# Connecters.net
KiCad netlist of a schematic drawn in Altium Designer
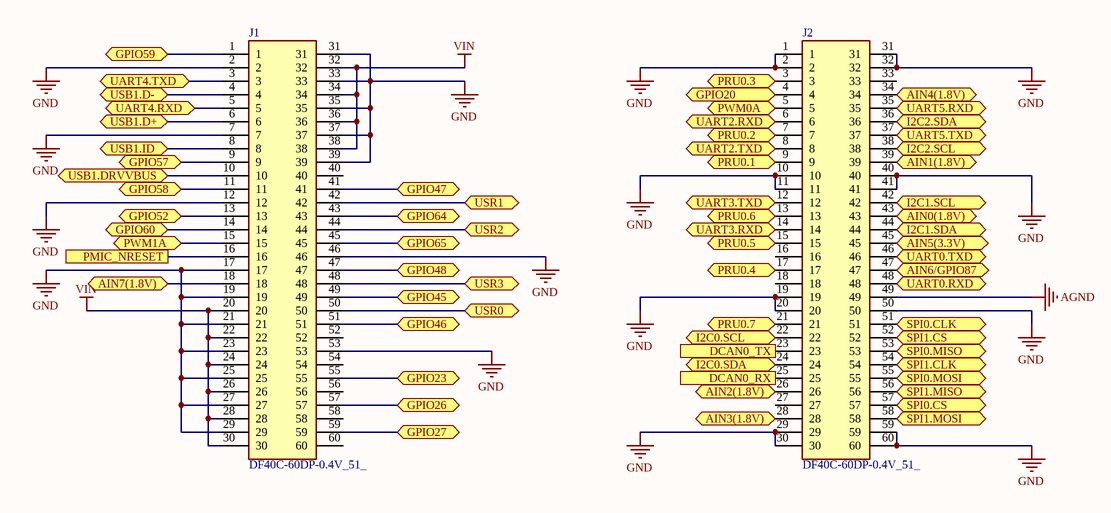
[diagram p0: Connecters.SchDoc]

(export (version "E")
  (design (tool "Eeschema 10.0.6"))
  (components
    (comp (ref "J1")
      (value "DF40C-60DP-0.4V_51_")
      (footprint "SamacSys:DF40C-60DP-0.4V(51)")
      (description "Connector")
      (fields
        (field (name "MANUFACTURER_PART_NUMBER") "DF40C-60DP-0.4V(51)")
        (field (name "MOUSER PART NUMBER") "798-DF40C60DP0.4V51")
      )
      (libsource (lib "Schlib1") (part "DF40C-60DP-0.4V_51_"))
    )
    (comp (ref "J2")
      (value "DF40C-60DP-0.4V_51_")
      (footprint "SamacSys:DF40C-60DP-0.4V(51)")
      (description "Connector")
      (fields
        (field (name "MANUFACTURER_PART_NUMBER") "DF40C-60DP-0.4V(51)")
        (field (name "MOUSER PART NUMBER") "798-DF40C60DP0.4V51")
      )
      (libsource (lib "Schlib1") (part "DF40C-60DP-0.4V_51_"))
    )
  )
  (nets
    (net (code "1") (name "/AIN0(1.8V)") (class "Default")
      (node (ref "J2") (pin "43") (pinfunction "43_43") (pintype "passive"))
    )
    (net (code "2") (name "/AIN1(1.8V)") (class "Default")
      (node (ref "J2") (pin "39") (pinfunction "39_39") (pintype "passive"))
    )
    (net (code "3") (name "/AIN2(1.8V)") (class "Default")
      (node (ref "J2") (pin "26") (pinfunction "26_26") (pintype "passive"))
    )
    (net (code "4") (name "/AIN3(1.8V)") (class "Default")
      (node (ref "J2") (pin "28") (pinfunction "28_28") (pintype "passive"))
    )
    (net (code "5") (name "/AIN4(1.8V)") (class "Default")
      (node (ref "J2") (pin "34") (pinfunction "34_34") (pintype "passive"))
    )
    (net (code "6") (name "/AIN5(3.3V)") (class "Default")
      (node (ref "J2") (pin "45") (pinfunction "45_45") (pintype "passive"))
    )
    (net (code "7") (name "/AIN6{slash}GPIO87") (class "Default")
      (node (ref "J2") (pin "47") (pinfunction "47_47") (pintype "passive"))
    )
    (net (code "8") (name "/AIN7(1.8V)") (class "Default")
      (node (ref "J1") (pin "18") (pinfunction "18_18") (pintype "passive"))
    )
    (net (code "9") (name "/DCAN0_RX") (class "Default")
      (node (ref "J2") (pin "25") (pinfunction "25_25") (pintype "passive"))
    )
    (net (code "10") (name "/DCAN0_TX") (class "Default")
      (node (ref "J2") (pin "23") (pinfunction "23_23") (pintype "passive"))
    )
    (net (code "11") (name "/GPIO20") (class "Default")
      (node (ref "J2") (pin "4") (pinfunction "4_4") (pintype "passive"))
    )
    (net (code "12") (name "/GPIO23") (class "Default")
      (node (ref "J1") (pin "55") (pinfunction "55_55") (pintype "passive"))
    )
    (net (code "13") (name "/GPIO26") (class "Default")
      (node (ref "J1") (pin "57") (pinfunction "57_57") (pintype "passive"))
    )
    (net (code "14") (name "/GPIO27") (class "Default")
      (node (ref "J1") (pin "59") (pinfunction "59_59") (pintype "passive"))
    )
    (net (code "15") (name "/GPIO45") (class "Default")
      (node (ref "J1") (pin "49") (pinfunction "49_49") (pintype "passive"))
    )
    (net (code "16") (name "/GPIO46") (class "Default")
      (node (ref "J1") (pin "51") (pinfunction "51_51") (pintype "passive"))
    )
    (net (code "17") (name "/GPIO47") (class "Default")
      (node (ref "J1") (pin "41") (pinfunction "41_41") (pintype "passive"))
    )
    (net (code "18") (name "/GPIO48") (class "Default")
      (node (ref "J1") (pin "47") (pinfunction "47_47") (pintype "passive"))
    )
    (net (code "19") (name "/GPIO52") (class "Default")
      (node (ref "J1") (pin "13") (pinfunction "13_13") (pintype "passive"))
    )
    (net (code "20") (name "/GPIO57") (class "Default")
      (node (ref "J1") (pin "9") (pinfunction "9_9") (pintype "passive"))
    )
    (net (code "21") (name "/GPIO58") (class "Default")
      (node (ref "J1") (pin "11") (pinfunction "11_11") (pintype "passive"))
    )
    (net (code "22") (name "/GPIO59") (class "Default")
      (node (ref "J1") (pin "1") (pinfunction "1_1") (pintype "passive"))
    )
    (net (code "23") (name "/GPIO60") (class "Default")
      (node (ref "J1") (pin "14") (pinfunction "14_14") (pintype "passive"))
    )
    (net (code "24") (name "/GPIO64") (class "Default")
      (node (ref "J1") (pin "43") (pinfunction "43_43") (pintype "passive"))
    )
    (net (code "25") (name "/GPIO65") (class "Default")
      (node (ref "J1") (pin "45") (pinfunction "45_45") (pintype "passive"))
    )
    (net (code "26") (name "/I2C0.SCL") (class "Default")
      (node (ref "J2") (pin "22") (pinfunction "22_22") (pintype "passive"))
    )
    (net (code "27") (name "/I2C0.SDA") (class "Default")
      (node (ref "J2") (pin "24") (pinfunction "24_24") (pintype "passive"))
    )
    (net (code "28") (name "/I2C1.SCL") (class "Default")
      (node (ref "J2") (pin "42") (pinfunction "42_42") (pintype "passive"))
    )
    (net (code "29") (name "/I2C1.SDA") (class "Default")
      (node (ref "J2") (pin "44") (pinfunction "44_44") (pintype "passive"))
    )
    (net (code "30") (name "/I2C2.SCL") (class "Default")
      (node (ref "J2") (pin "38") (pinfunction "38_38") (pintype "passive"))
    )
    (net (code "31") (name "/I2C2.SDA") (class "Default")
      (node (ref "J2") (pin "36") (pinfunction "36_36") (pintype "passive"))
    )
    (net (code "32") (name "/PMIC_NRESET") (class "Default")
      (node (ref "J1") (pin "16") (pinfunction "16_16") (pintype "passive"))
    )
    (net (code "33") (name "/PRU0.1") (class "Default")
      (node (ref "J2") (pin "9") (pinfunction "9_9") (pintype "passive"))
    )
    (net (code "34") (name "/PRU0.2") (class "Default")
      (node (ref "J2") (pin "7") (pinfunction "7_7") (pintype "passive"))
    )
    (net (code "35") (name "/PRU0.3") (class "Default")
      (node (ref "J2") (pin "3") (pinfunction "3_3") (pintype "passive"))
    )
    (net (code "36") (name "/PRU0.4") (class "Default")
      (node (ref "J2") (pin "17") (pinfunction "17_17") (pintype "passive"))
    )
    (net (code "37") (name "/PRU0.5") (class "Default")
      (node (ref "J2") (pin "15") (pinfunction "15_15") (pintype "passive"))
    )
    (net (code "38") (name "/PRU0.6") (class "Default")
      (node (ref "J2") (pin "13") (pinfunction "13_13") (pintype "passive"))
    )
    (net (code "39") (name "/PRU0.7") (class "Default")
      (node (ref "J2") (pin "21") (pinfunction "21_21") (pintype "passive"))
    )
    (net (code "40") (name "/PWM0A") (class "Default")
      (node (ref "J2") (pin "5") (pinfunction "5_5") (pintype "passive"))
    )
    (net (code "41") (name "/PWM1A") (class "Default")
      (node (ref "J1") (pin "15") (pinfunction "15_15") (pintype "passive"))
    )
    (net (code "42") (name "/SPI0.CLK") (class "Default")
      (node (ref "J2") (pin "51") (pinfunction "51_51") (pintype "passive"))
    )
    (net (code "43") (name "/SPI0.CS") (class "Default")
      (node (ref "J2") (pin "57") (pinfunction "57_57") (pintype "passive"))
    )
    (net (code "44") (name "/SPI0.MISO") (class "Default")
      (node (ref "J2") (pin "53") (pinfunction "53_53") (pintype "passive"))
    )
    (net (code "45") (name "/SPI0.MOSI") (class "Default")
      (node (ref "J2") (pin "55") (pinfunction "55_55") (pintype "passive"))
    )
    (net (code "46") (name "/SPI1.CLK") (class "Default")
      (node (ref "J2") (pin "54") (pinfunction "54_54") (pintype "passive"))
    )
    (net (code "47") (name "/SPI1.CS") (class "Default")
      (node (ref "J2") (pin "52") (pinfunction "52_52") (pintype "passive"))
    )
    (net (code "48") (name "/SPI1.MISO") (class "Default")
      (node (ref "J2") (pin "56") (pinfunction "56_56") (pintype "passive"))
    )
    (net (code "49") (name "/SPI1.MOSI") (class "Default")
      (node (ref "J2") (pin "58") (pinfunction "58_58") (pintype "passive"))
    )
    (net (code "50") (name "/UART0.RXD") (class "Default")
      (node (ref "J2") (pin "48") (pinfunction "48_48") (pintype "passive"))
    )
    (net (code "51") (name "/UART0.TXD") (class "Default")
      (node (ref "J2") (pin "46") (pinfunction "46_46") (pintype "passive"))
    )
    (net (code "52") (name "/UART2.RXD") (class "Default")
      (node (ref "J2") (pin "6") (pinfunction "6_6") (pintype "passive"))
    )
    (net (code "53") (name "/UART2.TXD") (class "Default")
      (node (ref "J2") (pin "8") (pinfunction "8_8") (pintype "passive"))
    )
    (net (code "54") (name "/UART3.RXD") (class "Default")
      (node (ref "J2") (pin "14") (pinfunction "14_14") (pintype "passive"))
    )
    (net (code "55") (name "/UART3.TXD") (class "Default")
      (node (ref "J2") (pin "12") (pinfunction "12_12") (pintype "passive"))
    )
    (net (code "56") (name "/UART4.RXD") (class "Default")
      (node (ref "J1") (pin "5") (pinfunction "5_5") (pintype "passive"))
    )
    (net (code "57") (name "/UART4.TXD") (class "Default")
      (node (ref "J1") (pin "3") (pinfunction "3_3") (pintype "passive"))
    )
    (net (code "58") (name "/UART5.RXD") (class "Default")
      (node (ref "J2") (pin "35") (pinfunction "35_35") (pintype "passive"))
    )
    (net (code "59") (name "/UART5.TXD") (class "Default")
      (node (ref "J2") (pin "37") (pinfunction "37_37") (pintype "passive"))
    )
    (net (code "60") (name "/USB1.D+") (class "Default")
      (node (ref "J1") (pin "6") (pinfunction "6_6") (pintype "passive"))
    )
    (net (code "61") (name "/USB1.D-") (class "Default")
      (node (ref "J1") (pin "4") (pinfunction "4_4") (pintype "passive"))
    )
    (net (code "62") (name "/USB1.DRVVBUS") (class "Default")
      (node (ref "J1") (pin "10") (pinfunction "10_10") (pintype "passive"))
    )
    (net (code "63") (name "/USB1.ID") (class "Default")
      (node (ref "J1") (pin "8") (pinfunction "8_8") (pintype "passive"))
    )
    (net (code "64") (name "/USR0") (class "Default")
      (node (ref "J1") (pin "50") (pinfunction "50_50") (pintype "passive"))
    )
    (net (code "65") (name "/USR1") (class "Default")
      (node (ref "J1") (pin "42") (pinfunction "42_42") (pintype "passive"))
    )
    (net (code "66") (name "/USR2") (class "Default")
      (node (ref "J1") (pin "44") (pinfunction "44_44") (pintype "passive"))
    )
    (net (code "67") (name "/USR3") (class "Default")
      (node (ref "J1") (pin "48") (pinfunction "48_48") (pintype "passive"))
    )
    (net (code "68") (name "AGND") (class "Default")
      (node (ref "J2") (pin "49") (pinfunction "49_49") (pintype "passive"))
    )
    (net (code "69") (name "GND") (class "Default")
      (node (ref "J1") (pin "12") (pinfunction "12_12") (pintype "passive"))
      (node (ref "J1") (pin "17") (pinfunction "17_17") (pintype "passive"))
      (node (ref "J1") (pin "19") (pinfunction "19_19") (pintype "passive"))
      (node (ref "J1") (pin "2") (pinfunction "2_2") (pintype "passive"))
      (node (ref "J1") (pin "21") (pinfunction "21_21") (pintype "passive"))
      (node (ref "J1") (pin "23") (pinfunction "23_23") (pintype "passive"))
      (node (ref "J1") (pin "25") (pinfunction "25_25") (pintype "passive"))
      (node (ref "J1") (pin "27") (pinfunction "27_27") (pintype "passive"))
      (node (ref "J1") (pin "29") (pinfunction "29_29") (pintype "passive"))
      (node (ref "J1") (pin "31") (pinfunction "31_31") (pintype "passive"))
      (node (ref "J1") (pin "33") (pinfunction "33_33") (pintype "passive"))
      (node (ref "J1") (pin "35") (pinfunction "35_35") (pintype "passive"))
      (node (ref "J1") (pin "37") (pinfunction "37_37") (pintype "passive"))
      (node (ref "J1") (pin "39") (pinfunction "39_39") (pintype "passive"))
      (node (ref "J1") (pin "46") (pinfunction "46_46") (pintype "passive"))
      (node (ref "J1") (pin "53") (pinfunction "53_53") (pintype "passive"))
      (node (ref "J1") (pin "7") (pinfunction "7_7") (pintype "passive"))
      (node (ref "J2") (pin "1") (pinfunction "1_1") (pintype "passive"))
      (node (ref "J2") (pin "10") (pinfunction "10_10") (pintype "passive"))
      (node (ref "J2") (pin "11") (pinfunction "11_11") (pintype "passive"))
      (node (ref "J2") (pin "19") (pinfunction "19_19") (pintype "passive"))
      (node (ref "J2") (pin "2") (pinfunction "2_2") (pintype "passive"))
      (node (ref "J2") (pin "20") (pinfunction "20_20") (pintype "passive"))
      (node (ref "J2") (pin "29") (pinfunction "29_29") (pintype "passive"))
      (node (ref "J2") (pin "30") (pinfunction "30_30") (pintype "passive"))
      (node (ref "J2") (pin "31") (pinfunction "31_31") (pintype "passive"))
      (node (ref "J2") (pin "32") (pinfunction "32_32") (pintype "passive"))
      (node (ref "J2") (pin "40") (pinfunction "40_40") (pintype "passive"))
      (node (ref "J2") (pin "41") (pinfunction "41_41") (pintype "passive"))
      (node (ref "J2") (pin "50") (pinfunction "50_50") (pintype "passive"))
      (node (ref "J2") (pin "59") (pinfunction "59_59") (pintype "passive"))
      (node (ref "J2") (pin "60") (pinfunction "60_60") (pintype "passive"))
    )
    (net (code "70") (name "VIN") (class "Default")
      (node (ref "J1") (pin "20") (pinfunction "20_20") (pintype "passive"))
      (node (ref "J1") (pin "22") (pinfunction "22_22") (pintype "passive"))
      (node (ref "J1") (pin "24") (pinfunction "24_24") (pintype "passive"))
      (node (ref "J1") (pin "26") (pinfunction "26_26") (pintype "passive"))
      (node (ref "J1") (pin "28") (pinfunction "28_28") (pintype "passive"))
      (node (ref "J1") (pin "30") (pinfunction "30_30") (pintype "passive"))
      (node (ref "J1") (pin "32") (pinfunction "32_32") (pintype "passive"))
      (node (ref "J1") (pin "34") (pinfunction "34_34") (pintype "passive"))
      (node (ref "J1") (pin "36") (pinfunction "36_36") (pintype "passive"))
      (node (ref "J1") (pin "38") (pinfunction "38_38") (pintype "passive"))
    )
    (net (code "71") (name "unconnected-(J1-Pad40)") (class "Default")
      (node (ref "J1") (pin "40") (pinfunction "40_40") (pintype "passive"))
    )
    (net (code "72") (name "unconnected-(J1-Pad52)") (class "Default")
      (node (ref "J1") (pin "52") (pinfunction "52_52") (pintype "passive"))
    )
    (net (code "73") (name "unconnected-(J1-Pad54)") (class "Default")
      (node (ref "J1") (pin "54") (pinfunction "54_54") (pintype "passive"))
    )
    (net (code "74") (name "unconnected-(J1-Pad56)") (class "Default")
      (node (ref "J1") (pin "56") (pinfunction "56_56") (pintype "passive"))
    )
    (net (code "75") (name "unconnected-(J1-Pad58)") (class "Default")
      (node (ref "J1") (pin "58") (pinfunction "58_58") (pintype "passive"))
    )
    (net (code "76") (name "unconnected-(J1-Pad60)") (class "Default")
      (node (ref "J1") (pin "60") (pinfunction "60_60") (pintype "passive"))
    )
    (net (code "77") (name "unconnected-(J2-Pad16)") (class "Default")
      (node (ref "J2") (pin "16") (pinfunction "16_16") (pintype "passive"))
    )
    (net (code "78") (name "unconnected-(J2-Pad18)") (class "Default")
      (node (ref "J2") (pin "18") (pinfunction "18_18") (pintype "passive"))
    )
    (net (code "79") (name "unconnected-(J2-Pad27)") (class "Default")
      (node (ref "J2") (pin "27") (pinfunction "27_27") (pintype "passive"))
    )
    (net (code "80") (name "unconnected-(J2-Pad33)") (class "Default")
      (node (ref "J2") (pin "33") (pinfunction "33_33") (pintype "passive"))
    )
  )
)
